# moddeducurrent.net
KiCad netlist of a schematic drawn in EAGLE
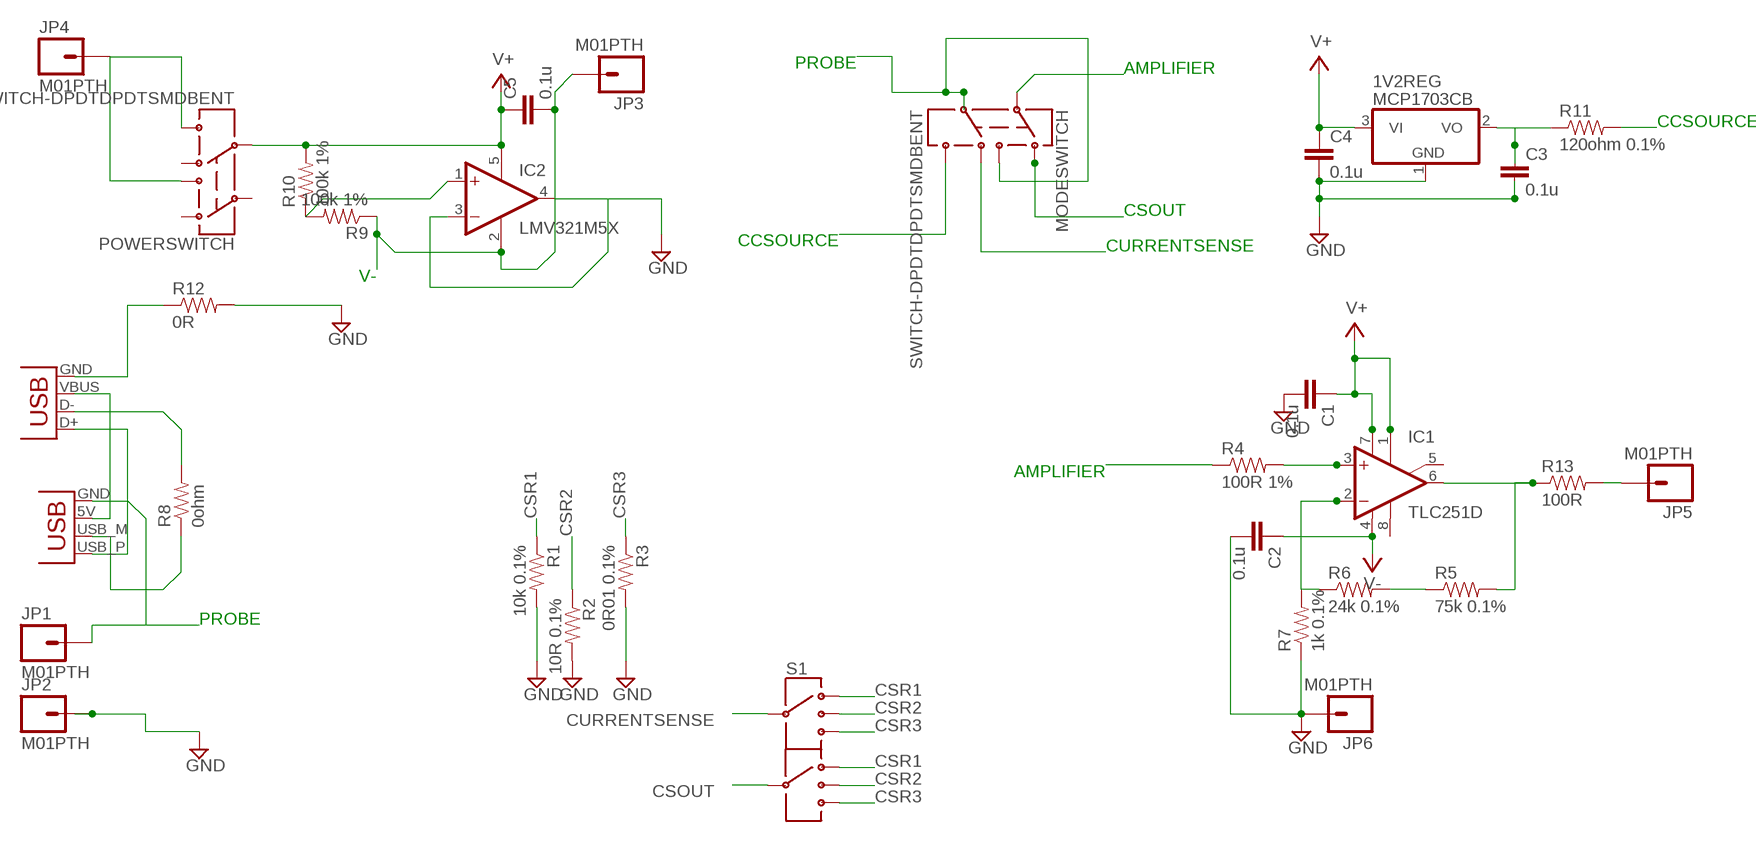
[diagram p0: schematic, sheet 1]

(export (version "E")
  (design (tool "Eeschema 10.0.6"))
  (components
    (comp (ref "1V2REG")
      (value "MCP1703CB")
      (footprint "eagle-import:SOT23")
      (libsource (lib "eagle-import") (part "MCP1703CB"))
    )
    (comp (ref "C1")
      (value "0.1u")
      (footprint "eagle-import:0805")
      (libsource (lib "eagle-import") (part "CAP0805"))
    )
    (comp (ref "C2")
      (value "0.1u")
      (footprint "eagle-import:0805")
      (libsource (lib "eagle-import") (part "CAP0805"))
    )
    (comp (ref "C3")
      (value "0.1u")
      (footprint "eagle-import:0805")
      (libsource (lib "eagle-import") (part "CAP0805"))
    )
    (comp (ref "C4")
      (value "0.1u")
      (footprint "eagle-import:0805")
      (libsource (lib "eagle-import") (part "CAP0805"))
    )
    (comp (ref "C5")
      (value "0.1u")
      (footprint "eagle-import:0805")
      (libsource (lib "eagle-import") (part "CAP0805"))
    )
    (comp (ref "IC1")
      (value "TLC251D")
      (footprint "eagle-import:SO08")
      (libsource (lib "eagle-import") (part "TLC251D"))
    )
    (comp (ref "IC2")
      (value "LMV321M5X")
      (footprint "eagle-import:SOT23-5")
      (libsource (lib "eagle-import") (part "LMV321?M5X"))
    )
    (comp (ref "JP1")
      (value "M01PTH")
      (footprint "eagle-import:1X01")
      (libsource (lib "eagle-import") (part "M01PTH"))
    )
    (comp (ref "JP2")
      (value "M01PTH")
      (footprint "eagle-import:1X01")
      (libsource (lib "eagle-import") (part "M01PTH"))
    )
    (comp (ref "JP3")
      (value "M01PTH")
      (footprint "eagle-import:1X01")
      (libsource (lib "eagle-import") (part "M01PTH"))
    )
    (comp (ref "JP4")
      (value "M01PTH")
      (footprint "eagle-import:1X01")
      (libsource (lib "eagle-import") (part "M01PTH"))
    )
    (comp (ref "JP5")
      (value "M01PTH")
      (footprint "eagle-import:1X01")
      (libsource (lib "eagle-import") (part "M01PTH"))
    )
    (comp (ref "JP6")
      (value "M01PTH")
      (footprint "eagle-import:1X01")
      (libsource (lib "eagle-import") (part "M01PTH"))
    )
    (comp (ref "MODESWITCH")
      (value "SWITCH-DPDTDPDTSMDBENT")
      (footprint "eagle-import:AYZ0202")
      (libsource (lib "eagle-import") (part "SWITCH-DPDTDPDTSMDBENT"))
    )
    (comp (ref "POWERSWITCH")
      (value "SWITCH-DPDTDPDTSMDBENT")
      (footprint "eagle-import:AYZ0202")
      (libsource (lib "eagle-import") (part "SWITCH-DPDTDPDTSMDBENT"))
    )
    (comp (ref "R1")
      (value "10k 0.1%")
      (footprint "eagle-import:0805")
      (libsource (lib "eagle-import") (part "RESISTOR0805-RES"))
    )
    (comp (ref "R2")
      (value "10R 0.1%")
      (footprint "eagle-import:0805")
      (libsource (lib "eagle-import") (part "RESISTOR0805-RES"))
    )
    (comp (ref "R3")
      (value "0R01 0.1%")
      (footprint "eagle-import:0805")
      (libsource (lib "eagle-import") (part "RESISTOR0805-RES"))
    )
    (comp (ref "R4")
      (value "100R 1%")
      (footprint "eagle-import:0805")
      (libsource (lib "eagle-import") (part "RESISTOR0805-RES"))
    )
    (comp (ref "R5")
      (value "75k 0.1%")
      (footprint "eagle-import:0805")
      (libsource (lib "eagle-import") (part "RESISTOR0805-RES"))
    )
    (comp (ref "R6")
      (value "24k 0.1%")
      (footprint "eagle-import:0805")
      (libsource (lib "eagle-import") (part "RESISTOR0805-RES"))
    )
    (comp (ref "R7")
      (value "1k 0.1%")
      (footprint "eagle-import:0805")
      (libsource (lib "eagle-import") (part "RESISTOR0805-RES"))
    )
    (comp (ref "R8")
      (value "0ohm")
      (footprint "eagle-import:0805")
      (libsource (lib "eagle-import") (part "RESISTOR0805-RES"))
    )
    (comp (ref "R9")
      (value "100k 1%")
      (footprint "eagle-import:0805")
      (libsource (lib "eagle-import") (part "RESISTOR0805-RES"))
    )
    (comp (ref "R10")
      (value "100k 1%")
      (footprint "eagle-import:0805")
      (libsource (lib "eagle-import") (part "RESISTOR0805-RES"))
    )
    (comp (ref "R11")
      (value "120ohm 0.1%")
      (footprint "eagle-import:0805")
      (libsource (lib "eagle-import") (part "RESISTOR0805-RES"))
    )
    (comp (ref "R12")
      (value "0R")
      (footprint "eagle-import:0805")
      (libsource (lib "eagle-import") (part "RESISTOR0805-RES"))
    )
    (comp (ref "R13")
      (value "100R")
      (footprint "eagle-import:0805")
      (libsource (lib "eagle-import") (part "RESISTOR0805-RES"))
    )
    (comp (ref "S1")
      (value "SWITCH-DP3T")
      (footprint "eagle-import:SWITCH-DP3T-SMD")
      (libsource (lib "eagle-import") (part "SWITCH-DP3T"))
    )
    (comp (ref "X1")
      (value "USBPCB")
      (footprint "eagle-import:USB-A-PCB")
      (libsource (lib "eagle-import") (part "USBPCB"))
    )
    (comp (ref "X2")
      (value "USBOLD")
      (footprint "eagle-import:USB-MINIB-OLD")
      (libsource (lib "eagle-import") (part "USBOLD"))
    )
  )
  (nets
    (net (code "1") (name "/AMPIN") (class "Default")
      (node (ref "MODESWITCH") (pin "2") (pinfunction "2_2") (pintype "bidirectional"))
      (node (ref "R4") (pin "1") (pinfunction "1_1") (pintype "passive"))
    )
    (net (code "2") (name "/CCSOURCE") (class "Default")
      (node (ref "MODESWITCH") (pin "6") (pinfunction "6_6") (pintype "bidirectional"))
      (node (ref "R11") (pin "2") (pinfunction "2_2") (pintype "passive"))
    )
    (net (code "3") (name "/CSOUT") (class "Default")
      (node (ref "MODESWITCH") (pin "1") (pinfunction "1_1") (pintype "bidirectional"))
      (node (ref "S1") (pin "BI") (pinfunction "BI_BI") (pintype "bidirectional"))
    )
    (net (code "4") (name "/CSR1") (class "Default")
      (node (ref "R1") (pin "1") (pinfunction "1_1") (pintype "passive"))
      (node (ref "S1") (pin "A1") (pinfunction "A1_A1") (pintype "bidirectional"))
      (node (ref "S1") (pin "B1") (pinfunction "B1_B1") (pintype "bidirectional"))
    )
    (net (code "5") (name "/CSR2") (class "Default")
      (node (ref "R2") (pin "1") (pinfunction "1_1") (pintype "passive"))
      (node (ref "S1") (pin "A2") (pinfunction "A2_A2") (pintype "bidirectional"))
      (node (ref "S1") (pin "B2") (pinfunction "B2_B2") (pintype "bidirectional"))
    )
    (net (code "6") (name "/CSR3") (class "Default")
      (node (ref "R3") (pin "1") (pinfunction "1_1") (pintype "passive"))
      (node (ref "S1") (pin "A3") (pinfunction "A3_A3") (pintype "bidirectional"))
      (node (ref "S1") (pin "B3") (pinfunction "B3_B3") (pintype "bidirectional"))
    )
    (net (code "7") (name "/CURRENTSENSE") (class "Default")
      (node (ref "MODESWITCH") (pin "4") (pinfunction "4_4") (pintype "bidirectional"))
      (node (ref "S1") (pin "AI") (pinfunction "AI_AI") (pintype "bidirectional"))
    )
    (net (code "8") (name "/PROBE") (class "Default")
      (node (ref "JP1") (pin "1") (pinfunction "1_1") (pintype "passive"))
      (node (ref "MODESWITCH") (pin "3") (pinfunction "3_3") (pintype "bidirectional"))
      (node (ref "MODESWITCH") (pin "5") (pinfunction "5_5") (pintype "bidirectional"))
      (node (ref "X1") (pin "GND") (pinfunction "GND_GND") (pintype "bidirectional"))
    )
    (net (code "9") (name "GND") (class "Default")
      (node (ref "1V2REG") (pin "1") (pinfunction "GND_1") (pintype "passive"))
      (node (ref "C1") (pin "2") (pinfunction "2_2") (pintype "passive"))
      (node (ref "C2") (pin "2") (pinfunction "2_2") (pintype "passive"))
      (node (ref "C3") (pin "2") (pinfunction "2_2") (pintype "passive"))
      (node (ref "C4") (pin "2") (pinfunction "2_2") (pintype "passive"))
      (node (ref "IC2") (pin "3") (pinfunction "-IN_3") (pintype "input"))
      (node (ref "IC2") (pin "4") (pinfunction "OUT_4") (pintype "output"))
      (node (ref "JP2") (pin "1") (pinfunction "1_1") (pintype "passive"))
      (node (ref "JP6") (pin "1") (pinfunction "1_1") (pintype "passive"))
      (node (ref "R1") (pin "2") (pinfunction "2_2") (pintype "passive"))
      (node (ref "R12") (pin "2") (pinfunction "2_2") (pintype "passive"))
      (node (ref "R2") (pin "2") (pinfunction "2_2") (pintype "passive"))
      (node (ref "R3") (pin "2") (pinfunction "2_2") (pintype "passive"))
      (node (ref "R7") (pin "1") (pinfunction "1_1") (pintype "passive"))
    )
    (net (code "10") (name "Net-(1V2REG-VO)") (class "Default")
      (node (ref "1V2REG") (pin "2") (pinfunction "VO_2") (pintype "passive"))
      (node (ref "C3") (pin "1") (pinfunction "1_1") (pintype "passive"))
      (node (ref "R11") (pin "1") (pinfunction "1_1") (pintype "passive"))
    )
    (net (code "11") (name "Net-(IC1-+IN)") (class "Default")
      (node (ref "IC1") (pin "3") (pinfunction "+IN_3") (pintype "input"))
      (node (ref "R4") (pin "2") (pinfunction "2_2") (pintype "passive"))
    )
    (net (code "12") (name "Net-(IC1--IN)") (class "Default")
      (node (ref "IC1") (pin "2") (pinfunction "-IN_2") (pintype "input"))
      (node (ref "R6") (pin "1") (pinfunction "1_1") (pintype "passive"))
      (node (ref "R7") (pin "2") (pinfunction "2_2") (pintype "passive"))
    )
    (net (code "13") (name "Net-(IC1-OUT)") (class "Default")
      (node (ref "IC1") (pin "6") (pinfunction "OUT_6") (pintype "output"))
      (node (ref "R13") (pin "1") (pinfunction "1_1") (pintype "passive"))
      (node (ref "R5") (pin "2") (pinfunction "2_2") (pintype "passive"))
    )
    (net (code "14") (name "Net-(IC2-+IN)") (class "Default")
      (node (ref "IC2") (pin "1") (pinfunction "+IN_1") (pintype "input"))
      (node (ref "R10") (pin "1") (pinfunction "1_1") (pintype "passive"))
      (node (ref "R9") (pin "2") (pinfunction "2_2") (pintype "passive"))
    )
    (net (code "15") (name "Net-(JP4-Pad1)") (class "Default")
      (node (ref "JP4") (pin "1") (pinfunction "1_1") (pintype "passive"))
      (node (ref "POWERSWITCH") (pin "3") (pinfunction "3_3") (pintype "bidirectional"))
      (node (ref "POWERSWITCH") (pin "6") (pinfunction "6_6") (pintype "bidirectional"))
    )
    (net (code "16") (name "Net-(JP5-Pad1)") (class "Default")
      (node (ref "JP5") (pin "1") (pinfunction "1_1") (pintype "passive"))
      (node (ref "R13") (pin "2") (pinfunction "2_2") (pintype "passive"))
    )
    (net (code "17") (name "Net-(R5-Pad1)") (class "Default")
      (node (ref "R5") (pin "1") (pinfunction "1_1") (pintype "passive"))
      (node (ref "R6") (pin "2") (pinfunction "2_2") (pintype "passive"))
    )
    (net (code "18") (name "Net-(R8-Pad2)") (class "Default")
      (node (ref "R8") (pin "2") (pinfunction "2_2") (pintype "passive"))
      (node (ref "X2") (pin "D-") (pinfunction "D-_D-") (pintype "bidirectional"))
    )
    (net (code "19") (name "Net-(R12-Pad1)") (class "Default")
      (node (ref "R12") (pin "1") (pinfunction "1_1") (pintype "passive"))
      (node (ref "X2") (pin "GND") (pinfunction "GND_GND") (pintype "bidirectional"))
    )
    (net (code "20") (name "Net-(X1-D+)") (class "Default")
      (node (ref "X1") (pin "USB_P") (pinfunction "D+_USB_P") (pintype "bidirectional"))
      (node (ref "X2") (pin "D+") (pinfunction "D+_D+") (pintype "bidirectional"))
    )
    (net (code "21") (name "Net-(X1-D-)") (class "Default")
      (node (ref "R8") (pin "1") (pinfunction "1_1") (pintype "passive"))
      (node (ref "X1") (pin "USB_M") (pinfunction "D-_USB_M") (pintype "bidirectional"))
    )
    (net (code "22") (name "Net-(X1-VBUS)") (class "Default")
      (node (ref "X1") (pin "5V") (pinfunction "VBUS_5V") (pintype "bidirectional"))
      (node (ref "X2") (pin "VBUS") (pinfunction "VBUS_VBUS") (pintype "bidirectional"))
    )
    (net (code "23") (name "V+") (class "Default")
      (node (ref "1V2REG") (pin "3") (pinfunction "VI_3") (pintype "input"))
      (node (ref "C1") (pin "1") (pinfunction "1_1") (pintype "passive"))
      (node (ref "C4") (pin "1") (pinfunction "1_1") (pintype "passive"))
      (node (ref "C5") (pin "1") (pinfunction "1_1") (pintype "passive"))
      (node (ref "IC1") (pin "1") (pinfunction "ON1_1") (pintype "passive"))
      (node (ref "IC1") (pin "7") (pinfunction "V+_7") (pintype "power_in"))
      (node (ref "IC2") (pin "5") (pinfunction "V+_5") (pintype "power_in"))
      (node (ref "POWERSWITCH") (pin "5") (pinfunction "5_5") (pintype "bidirectional"))
      (node (ref "R10") (pin "2") (pinfunction "2_2") (pintype "passive"))
    )
    (net (code "24") (name "V-") (class "Default")
      (node (ref "C2") (pin "1") (pinfunction "1_1") (pintype "passive"))
      (node (ref "C5") (pin "2") (pinfunction "2_2") (pintype "passive"))
      (node (ref "IC1") (pin "4") (pinfunction "V-_4") (pintype "power_in"))
      (node (ref "IC2") (pin "2") (pinfunction "V-_2") (pintype "power_in"))
      (node (ref "JP3") (pin "1") (pinfunction "1_1") (pintype "passive"))
      (node (ref "R9") (pin "1") (pinfunction "1_1") (pintype "passive"))
    )
    (net (code "25") (name "unconnected-(IC1-ON2-Pad5)") (class "Default")
      (node (ref "IC1") (pin "5") (pinfunction "ON2_5") (pintype "passive"))
    )
    (net (code "26") (name "unconnected-(IC1-OPT-Pad8)") (class "Default")
      (node (ref "IC1") (pin "8") (pinfunction "OPT_8") (pintype "passive"))
    )
    (net (code "27") (name "unconnected-(POWERSWITCH-Pad1)") (class "Default")
      (node (ref "POWERSWITCH") (pin "1") (pinfunction "1_1") (pintype "bidirectional"))
    )
    (net (code "28") (name "unconnected-(POWERSWITCH-Pad2)") (class "Default")
      (node (ref "POWERSWITCH") (pin "2") (pinfunction "2_2") (pintype "bidirectional"))
    )
    (net (code "29") (name "unconnected-(POWERSWITCH-Pad4)") (class "Default")
      (node (ref "POWERSWITCH") (pin "4") (pinfunction "4_4") (pintype "bidirectional"))
    )
  )
)
